# design.net
KiCad netlist of a schematic drawn in Altium Designer
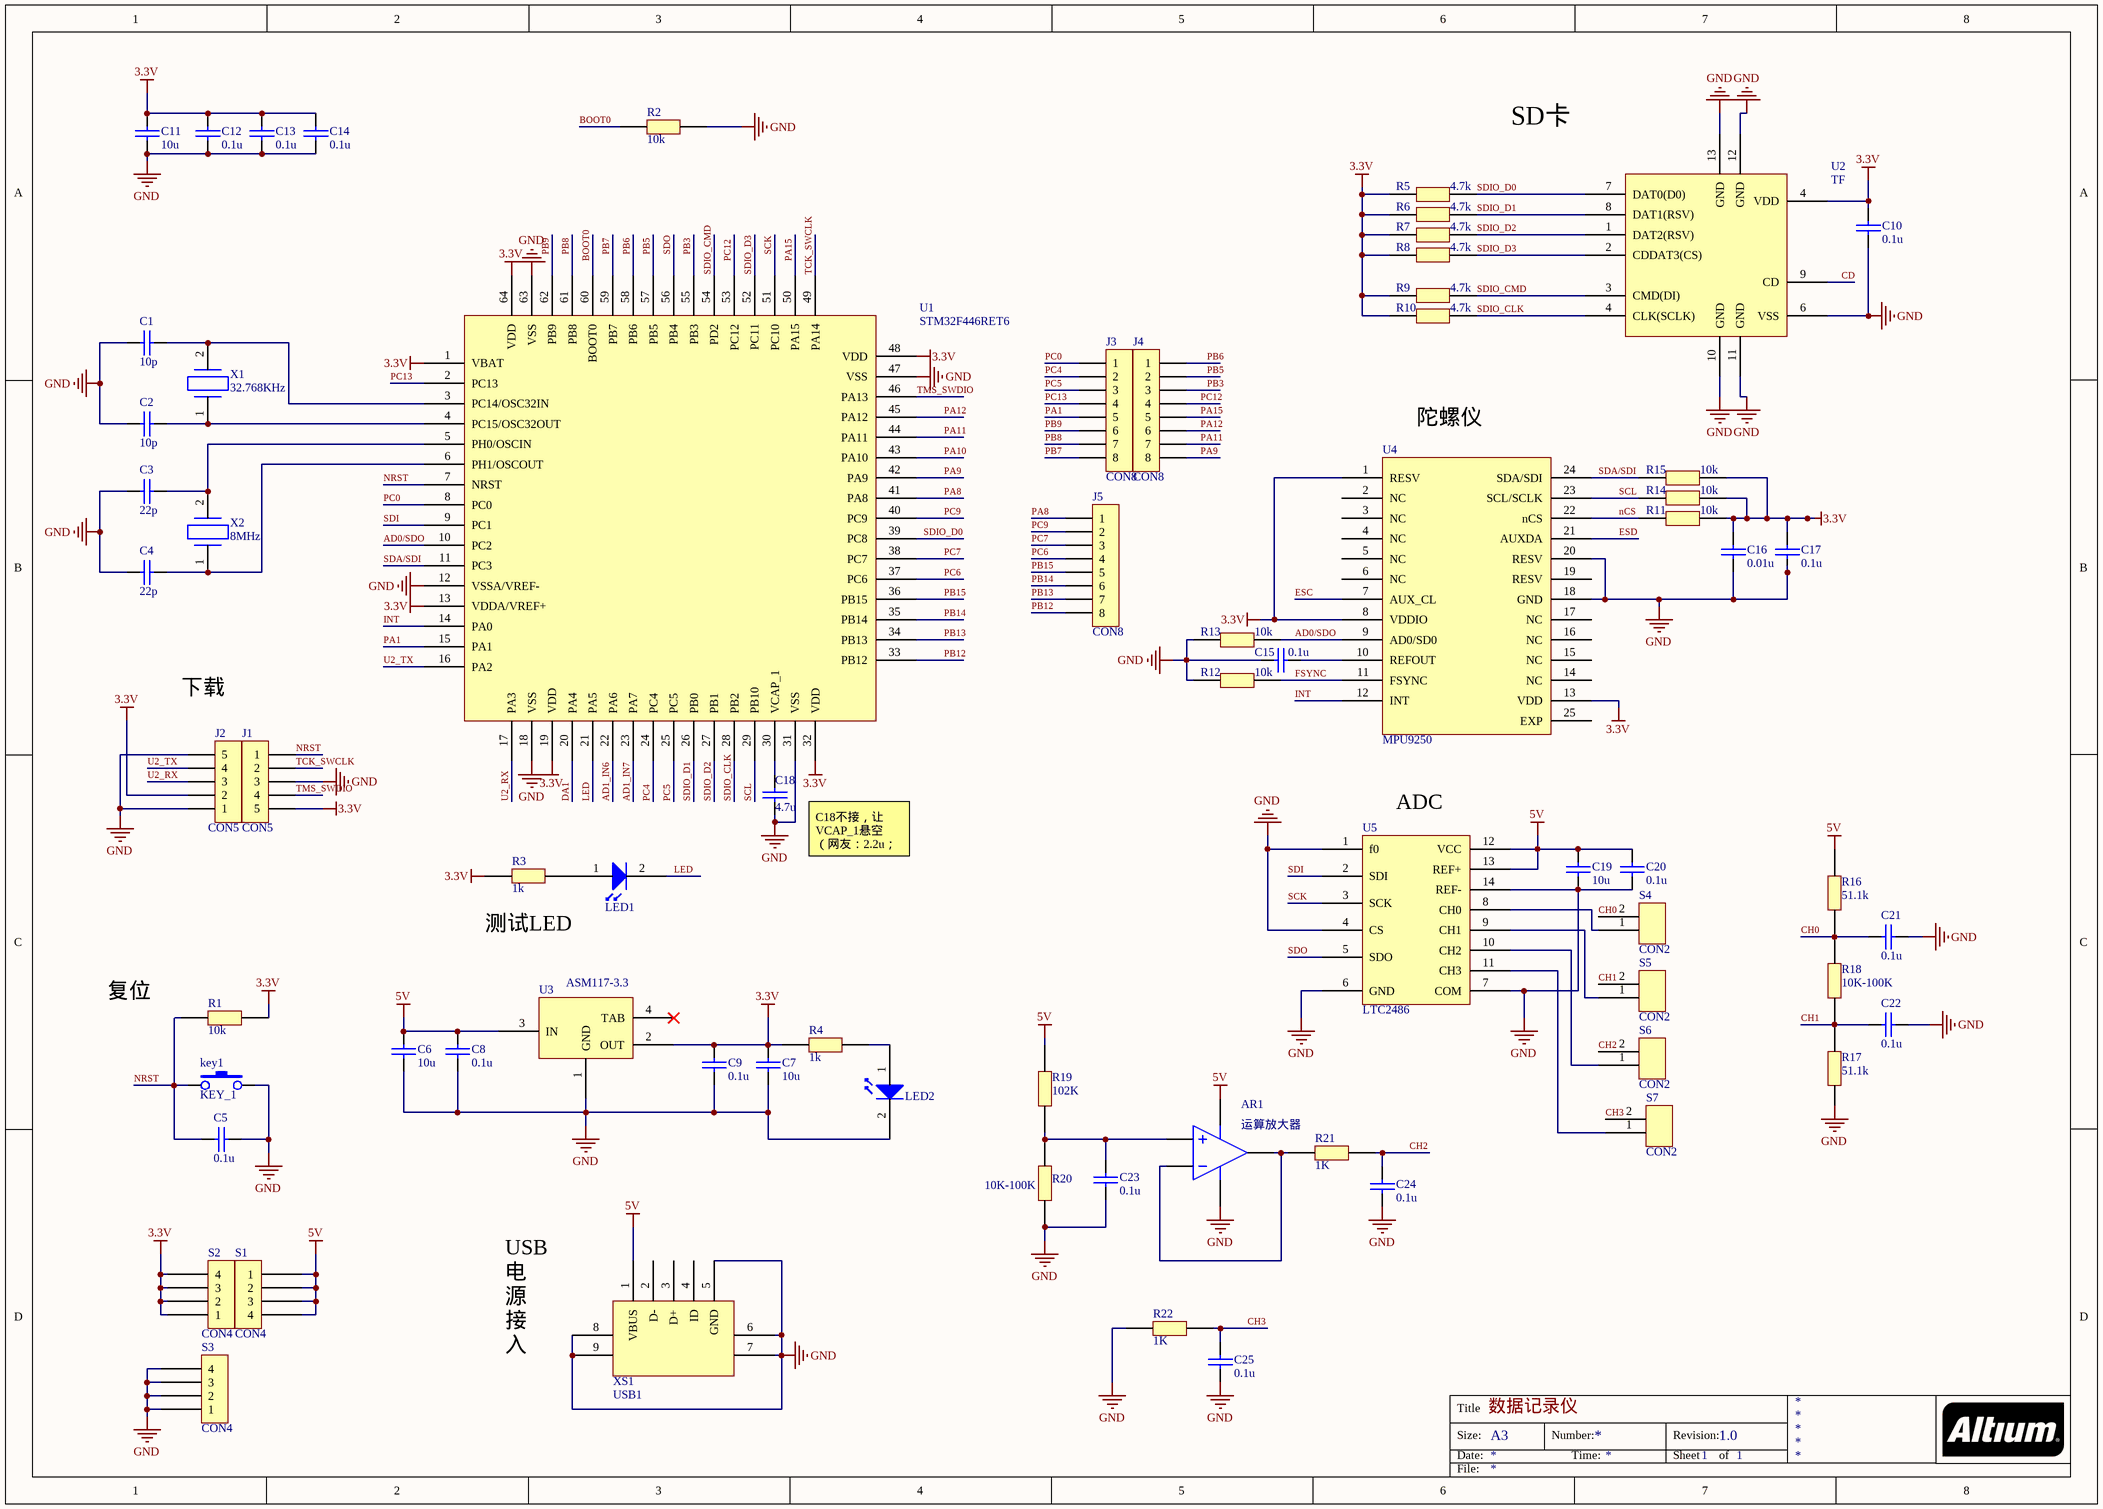
[diagram p0: 数据记录仪.SchDoc]

(export (version "E")
  (design (tool "Eeschema 10.0.6"))
  (components
    (comp (ref "AR1")
      (value "运算放大器")
      (footprint "MSOP-8")
      (description "Operational Amplifier")
      (libsource (lib "元件库") (part "运算放大器"))
    )
    (comp (ref "C1") (value "10p") (footprint "0603-cap") (libsource (lib "元件库") (part "CAP")))
    (comp (ref "C2") (value "10p") (footprint "0603-cap") (libsource (lib "元件库") (part "CAP")))
    (comp (ref "C3") (value "22p") (footprint "0603-cap") (libsource (lib "元件库") (part "CAP")))
    (comp (ref "C4") (value "22p") (footprint "0603-cap") (libsource (lib "元件库") (part "CAP")))
    (comp (ref "C5") (value "0.1u") (footprint "0603-cap") (libsource (lib "元件库") (part "CAP")))
    (comp (ref "C6") (value "10u") (footprint "0603-cap") (libsource (lib "元件库") (part "CAP")))
    (comp (ref "C7") (value "10u") (footprint "0603-cap") (libsource (lib "元件库") (part "CAP")))
    (comp (ref "C8") (value "0.1u") (footprint "0603-cap") (libsource (lib "元件库") (part "CAP")))
    (comp (ref "C9") (value "0.1u") (footprint "0603-cap") (libsource (lib "元件库") (part "CAP")))
    (comp (ref "C10") (value "0.1u") (footprint "0603-cap") (libsource (lib "元件库") (part "CAP")))
    (comp (ref "C11") (value "10u") (footprint "0603-cap") (libsource (lib "元件库") (part "CAP")))
    (comp (ref "C12") (value "0.1u") (footprint "0603-cap") (libsource (lib "元件库") (part "CAP")))
    (comp (ref "C13") (value "0.1u") (footprint "0603-cap") (libsource (lib "元件库") (part "CAP")))
    (comp (ref "C14") (value "0.1u") (footprint "0603-cap") (libsource (lib "元件库") (part "CAP")))
    (comp (ref "C15") (value "0.1u") (footprint "0603-cap") (libsource (lib "元件库") (part "CAP")))
    (comp (ref "C16") (value "0.01u") (footprint "0603-cap") (libsource (lib "元件库") (part "CAP")))
    (comp (ref "C17") (value "0.1u") (footprint "0603-cap") (libsource (lib "元件库") (part "CAP")))
    (comp (ref "C18") (value "4.7u") (footprint "0603-cap") (libsource (lib "元件库") (part "CAP")))
    (comp (ref "C19") (value "10u") (footprint "0603-cap") (libsource (lib "元件库") (part "CAP")))
    (comp (ref "C20") (value "0.1u") (footprint "0603-cap") (libsource (lib "元件库") (part "CAP")))
    (comp (ref "C21") (value "0.1u") (footprint "0603-cap") (libsource (lib "元件库") (part "CAP")))
    (comp (ref "C22") (value "0.1u") (footprint "0603-cap") (libsource (lib "元件库") (part "CAP")))
    (comp (ref "C23") (value "0.1u") (footprint "0603-cap") (libsource (lib "元件库") (part "CAP")))
    (comp (ref "C24") (value "0.1u") (footprint "0603-cap") (libsource (lib "元件库") (part "CAP")))
    (comp (ref "C25") (value "0.1u") (footprint "0603-cap") (libsource (lib "元件库") (part "CAP")))
    (comp (ref "J1") (value "CON5") (footprint "SIP05") (libsource (lib "") (part "CON5_1")))
    (comp (ref "J2") (value "CON5") (footprint "SIP05") (libsource (lib "元件库") (part "CON5")))
    (comp (ref "J3") (value "CON8") (footprint "SIP08") (libsource (lib "") (part "CON8_1")))
    (comp (ref "J4") (value "CON8") (footprint "SIP08") (libsource (lib "元件库") (part "CON8")))
    (comp (ref "J5") (value "CON8") (footprint "SIP08") (libsource (lib "") (part "CON8_1")))
    (comp (ref "key1") (value "KEY_1") (footprint "key - duplicate5") (libsource (lib "元件库") (part "KEY_1")))
    (comp (ref "LED1") (value "LED?") (footprint "LED") (libsource (lib "元件库") (part "LED")))
    (comp (ref "LED2") (value "LED?") (footprint "LED") (libsource (lib "元件库") (part "LED")))
    (comp (ref "R1") (value "10k") (footprint "0603-res") (libsource (lib "") (part "RES_1")))
    (comp (ref "R2") (value "10k") (footprint "0603-res") (libsource (lib "") (part "RES_1")))
    (comp (ref "R3") (value "1k") (footprint "0603-res") (libsource (lib "") (part "RES_1")))
    (comp (ref "R4") (value "1k") (footprint "0603-res") (libsource (lib "元件库") (part "RES")))
    (comp (ref "R5") (value "4.7k") (footprint "0603-res") (libsource (lib "元件库") (part "RES")))
    (comp (ref "R6") (value "4.7k") (footprint "0603-res") (libsource (lib "元件库") (part "RES")))
    (comp (ref "R7") (value "4.7k") (footprint "0603-res") (libsource (lib "元件库") (part "RES")))
    (comp (ref "R8") (value "4.7k") (footprint "0603-res") (libsource (lib "元件库") (part "RES")))
    (comp (ref "R9") (value "4.7k") (footprint "0603-res") (libsource (lib "元件库") (part "RES")))
    (comp (ref "R10") (value "4.7k") (footprint "0603-res") (libsource (lib "元件库") (part "RES")))
    (comp (ref "R11") (value "10k") (footprint "0603-res") (libsource (lib "元件库") (part "RES")))
    (comp (ref "R12") (value "10k") (footprint "0603-res") (libsource (lib "元件库") (part "RES")))
    (comp (ref "R13") (value "10k") (footprint "0603-res") (libsource (lib "元件库") (part "RES")))
    (comp (ref "R14") (value "10k") (footprint "0603-res") (libsource (lib "元件库") (part "RES")))
    (comp (ref "R15") (value "10k") (footprint "0603-res") (libsource (lib "元件库") (part "RES")))
    (comp (ref "R16") (value "51.1k") (footprint "0603-res") (libsource (lib "") (part "RES_2")))
    (comp (ref "R17") (value "51.1k") (footprint "0603-res") (libsource (lib "") (part "RES_2")))
    (comp (ref "R18") (value "10K-100K") (footprint "0603-res") (libsource (lib "") (part "RES_2")))
    (comp (ref "R19") (value "102K") (footprint "0603-res") (libsource (lib "") (part "RES_2")))
    (comp (ref "R20") (value "10K-100K") (footprint "0603-res") (libsource (lib "") (part "RES_2")))
    (comp (ref "R21") (value "1K") (footprint "0603-res") (libsource (lib "") (part "RES_1")))
    (comp (ref "R22") (value "1K") (footprint "0603-res") (libsource (lib "") (part "RES_1")))
    (comp (ref "S1") (value "CON4") (footprint "SIP04") (libsource (lib "") (part "CON4_1")))
    (comp (ref "S2") (value "CON4") (footprint "SIP04") (libsource (lib "元件库") (part "CON4")))
    (comp (ref "S3") (value "CON4") (footprint "SIP04") (libsource (lib "元件库") (part "CON4")))
    (comp (ref "S4") (value "CON2") (footprint "SIP02") (libsource (lib "元件库") (part "CON2")))
    (comp (ref "S5") (value "CON2") (footprint "SIP02") (libsource (lib "元件库") (part "CON2")))
    (comp (ref "S6") (value "CON2") (footprint "SIP02") (libsource (lib "元件库") (part "CON2")))
    (comp (ref "S7") (value "CON2") (footprint "SIP02") (libsource (lib "元件库") (part "CON2")))
    (comp (ref "U1")
      (value "STM32F446RET6")
      (footprint "LQFP-64_10X10X05P")
      (libsource (lib "元件库") (part "STM32F446RET6"))
    )
    (comp (ref "U2") (value "TF") (footprint "TF-01A") (libsource (lib "元件库") (part "TF-01A")))
    (comp (ref "U3") (value "ASM117-3.3") (footprint "SOT-223") (libsource (lib "元件库") (part "ASM117-3.3")))
    (comp (ref "U4")
      (value "MPU9250")
      (footprint "QFN-24-1EP_3X3MM_PITCH0.4MM")
      (libsource (lib "元件库") (part "MPU9250"))
    )
    (comp (ref "U5") (value "LTC2486") (footprint "DFN14") (libsource (lib "元件库") (part "LTC2486")))
    (comp (ref "X1") (value "32.768KHz") (footprint "XTAL2") (libsource (lib "元件库") (part "XTAL")))
    (comp (ref "X2") (value "8MHz") (footprint "XTAL2") (libsource (lib "元件库") (part "XTAL")))
    (comp (ref "XS1") (value "USB1") (footprint "micro USB") (libsource (lib "元件库") (part "USB1")))
  )
  (nets
    (net (code "1") (name "/AD0{slash}SDO") (class "Default")
      (node (ref "R13") (pin "2") (pinfunction "2_2") (pintype "passive"))
      (node (ref "U1") (pin "10") (pinfunction "PC2_10") (pintype "passive"))
      (node (ref "U4") (pin "9") (pinfunction "AD0/SD0_9") (pintype "passive"))
    )
    (net (code "2") (name "/AD1_IN6") (class "Default")
      (node (ref "U1") (pin "22") (pinfunction "PA6_22") (pintype "passive"))
    )
    (net (code "3") (name "/AD1_IN7") (class "Default")
      (node (ref "U1") (pin "23") (pinfunction "PA7_23") (pintype "passive"))
    )
    (net (code "4") (name "/BOOT0") (class "Default")
      (node (ref "R2") (pin "2") (pinfunction "2_2") (pintype "passive"))
      (node (ref "U1") (pin "60") (pinfunction "BOOT0_60") (pintype "passive"))
    )
    (net (code "5") (name "/CD") (class "Default")
      (node (ref "U2") (pin "9") (pinfunction "CD_9") (pintype "passive"))
    )
    (net (code "6") (name "/CH0") (class "Default")
      (node (ref "C21") (pin "1") (pinfunction "1_1") (pintype "passive"))
      (node (ref "R16") (pin "1") (pinfunction "1_1") (pintype "passive"))
      (node (ref "R18") (pin "2") (pinfunction "2_2") (pintype "passive"))
      (node (ref "S4") (pin "2") (pinfunction "2_2") (pintype "passive"))
    )
    (net (code "7") (name "/CH1") (class "Default")
      (node (ref "C22") (pin "2") (pinfunction "2_2") (pintype "passive"))
      (node (ref "R17") (pin "2") (pinfunction "2_2") (pintype "passive"))
      (node (ref "R18") (pin "1") (pinfunction "1_1") (pintype "passive"))
      (node (ref "S5") (pin "2") (pinfunction "2_2") (pintype "passive"))
    )
    (net (code "8") (name "/CH2") (class "Default")
      (node (ref "C24") (pin "1") (pinfunction "1_1") (pintype "passive"))
      (node (ref "R21") (pin "1") (pinfunction "1_1") (pintype "passive"))
      (node (ref "S6") (pin "2") (pinfunction "2_2") (pintype "passive"))
    )
    (net (code "9") (name "/CH3") (class "Default")
      (node (ref "C25") (pin "1") (pinfunction "1_1") (pintype "passive"))
      (node (ref "R22") (pin "1") (pinfunction "1_1") (pintype "passive"))
      (node (ref "S7") (pin "2") (pinfunction "2_2") (pintype "passive"))
    )
    (net (code "10") (name "/DA1") (class "Default")
      (node (ref "U1") (pin "20") (pinfunction "PA4_20") (pintype "passive"))
    )
    (net (code "11") (name "/ESC") (class "Default")
      (node (ref "U4") (pin "7") (pinfunction "AUX_CL_7") (pintype "passive"))
    )
    (net (code "12") (name "/ESD") (class "Default")
      (node (ref "U4") (pin "21") (pinfunction "AUXDA_21") (pintype "passive"))
    )
    (net (code "13") (name "/FSYNC") (class "Default")
      (node (ref "R12") (pin "2") (pinfunction "2_2") (pintype "passive"))
      (node (ref "U4") (pin "11") (pinfunction "FSYNC_11") (pintype "passive"))
    )
    (net (code "14") (name "/INT") (class "Default")
      (node (ref "U1") (pin "14") (pinfunction "PA0_14") (pintype "passive"))
      (node (ref "U4") (pin "12") (pinfunction "INT_12") (pintype "passive"))
    )
    (net (code "15") (name "/LED") (class "Default")
      (node (ref "LED1") (pin "2") (pinfunction "2_2") (pintype "passive"))
      (node (ref "U1") (pin "21") (pinfunction "PA5_21") (pintype "passive"))
    )
    (net (code "16") (name "/NRST") (class "Default")
      (node (ref "C5") (pin "1") (pinfunction "1_1") (pintype "passive"))
      (node (ref "J1") (pin "1") (pinfunction "1_1") (pintype "passive"))
      (node (ref "R1") (pin "2") (pinfunction "2_2") (pintype "passive"))
      (node (ref "U1") (pin "7") (pinfunction "NRST_7") (pintype "passive"))
      (node (ref "key1") (pin "1") (pinfunction "1_1") (pintype "passive"))
    )
    (net (code "17") (name "/PA1") (class "Default")
      (node (ref "J3") (pin "5") (pinfunction "5_5") (pintype "passive"))
      (node (ref "U1") (pin "15") (pinfunction "PA1_15") (pintype "passive"))
    )
    (net (code "18") (name "/PA8") (class "Default")
      (node (ref "J5") (pin "1") (pinfunction "1_1") (pintype "passive"))
      (node (ref "U1") (pin "41") (pinfunction "PA8_41") (pintype "passive"))
    )
    (net (code "19") (name "/PA9") (class "Default")
      (node (ref "J4") (pin "8") (pinfunction "8_8") (pintype "passive"))
      (node (ref "U1") (pin "42") (pinfunction "PA9_42") (pintype "passive"))
    )
    (net (code "20") (name "/PA10") (class "Default")
      (node (ref "U1") (pin "43") (pinfunction "PA10_43") (pintype "passive"))
    )
    (net (code "21") (name "/PA11") (class "Default")
      (node (ref "J4") (pin "7") (pinfunction "7_7") (pintype "passive"))
      (node (ref "U1") (pin "44") (pinfunction "PA11_44") (pintype "passive"))
    )
    (net (code "22") (name "/PA12") (class "Default")
      (node (ref "J4") (pin "6") (pinfunction "6_6") (pintype "passive"))
      (node (ref "U1") (pin "45") (pinfunction "PA12_45") (pintype "passive"))
    )
    (net (code "23") (name "/PA15") (class "Default")
      (node (ref "J4") (pin "5") (pinfunction "5_5") (pintype "passive"))
      (node (ref "U1") (pin "50") (pinfunction "PA15_50") (pintype "passive"))
    )
    (net (code "24") (name "/PB3") (class "Default")
      (node (ref "J4") (pin "3") (pinfunction "3_3") (pintype "passive"))
      (node (ref "U1") (pin "55") (pinfunction "PB3_55") (pintype "passive"))
    )
    (net (code "25") (name "/PB5") (class "Default")
      (node (ref "J4") (pin "2") (pinfunction "2_2") (pintype "passive"))
      (node (ref "U1") (pin "57") (pinfunction "PB5_57") (pintype "passive"))
    )
    (net (code "26") (name "/PB6") (class "Default")
      (node (ref "J4") (pin "1") (pinfunction "1_1") (pintype "passive"))
      (node (ref "U1") (pin "58") (pinfunction "PB6_58") (pintype "passive"))
    )
    (net (code "27") (name "/PB7") (class "Default")
      (node (ref "J3") (pin "8") (pinfunction "8_8") (pintype "passive"))
      (node (ref "U1") (pin "59") (pinfunction "PB7_59") (pintype "passive"))
    )
    (net (code "28") (name "/PB8") (class "Default")
      (node (ref "J3") (pin "7") (pinfunction "7_7") (pintype "passive"))
      (node (ref "U1") (pin "61") (pinfunction "PB8_61") (pintype "passive"))
    )
    (net (code "29") (name "/PB9") (class "Default")
      (node (ref "J3") (pin "6") (pinfunction "6_6") (pintype "passive"))
      (node (ref "U1") (pin "62") (pinfunction "PB9_62") (pintype "passive"))
    )
    (net (code "30") (name "/PB12") (class "Default")
      (node (ref "J5") (pin "8") (pinfunction "8_8") (pintype "passive"))
      (node (ref "U1") (pin "33") (pinfunction "PB12_33") (pintype "passive"))
    )
    (net (code "31") (name "/PB13") (class "Default")
      (node (ref "J5") (pin "7") (pinfunction "7_7") (pintype "passive"))
      (node (ref "U1") (pin "34") (pinfunction "PB13_34") (pintype "passive"))
    )
    (net (code "32") (name "/PB14") (class "Default")
      (node (ref "J5") (pin "6") (pinfunction "6_6") (pintype "passive"))
      (node (ref "U1") (pin "35") (pinfunction "PB14_35") (pintype "passive"))
    )
    (net (code "33") (name "/PB15") (class "Default")
      (node (ref "J5") (pin "5") (pinfunction "5_5") (pintype "passive"))
      (node (ref "U1") (pin "36") (pinfunction "PB15_36") (pintype "passive"))
    )
    (net (code "34") (name "/PC0") (class "Default")
      (node (ref "J3") (pin "1") (pinfunction "1_1") (pintype "passive"))
      (node (ref "U1") (pin "8") (pinfunction "PC0_8") (pintype "passive"))
    )
    (net (code "35") (name "/PC4") (class "Default")
      (node (ref "J3") (pin "2") (pinfunction "2_2") (pintype "passive"))
      (node (ref "U1") (pin "24") (pinfunction "PC4_24") (pintype "passive"))
    )
    (net (code "36") (name "/PC5") (class "Default")
      (node (ref "J3") (pin "3") (pinfunction "3_3") (pintype "passive"))
      (node (ref "U1") (pin "25") (pinfunction "PC5_25") (pintype "passive"))
    )
    (net (code "37") (name "/PC6") (class "Default")
      (node (ref "J5") (pin "4") (pinfunction "4_4") (pintype "passive"))
      (node (ref "U1") (pin "37") (pinfunction "PC6_37") (pintype "passive"))
    )
    (net (code "38") (name "/PC7") (class "Default")
      (node (ref "J5") (pin "3") (pinfunction "3_3") (pintype "passive"))
      (node (ref "U1") (pin "38") (pinfunction "PC7_38") (pintype "passive"))
    )
    (net (code "39") (name "/PC9") (class "Default")
      (node (ref "J5") (pin "2") (pinfunction "2_2") (pintype "passive"))
      (node (ref "U1") (pin "40") (pinfunction "PC9_40") (pintype "passive"))
    )
    (net (code "40") (name "/PC12") (class "Default")
      (node (ref "J4") (pin "4") (pinfunction "4_4") (pintype "passive"))
      (node (ref "U1") (pin "53") (pinfunction "PC12_53") (pintype "passive"))
    )
    (net (code "41") (name "/PC13") (class "Default")
      (node (ref "J3") (pin "4") (pinfunction "4_4") (pintype "passive"))
      (node (ref "U1") (pin "2") (pinfunction "PC13_2") (pintype "passive"))
    )
    (net (code "42") (name "/SCK") (class "Default")
      (node (ref "U1") (pin "51") (pinfunction "PC10_51") (pintype "passive"))
      (node (ref "U5") (pin "3") (pinfunction "SCK_3") (pintype "passive"))
    )
    (net (code "43") (name "/SCL") (class "Default")
      (node (ref "R14") (pin "1") (pinfunction "1_1") (pintype "passive"))
      (node (ref "U1") (pin "29") (pinfunction "PB10_29") (pintype "passive"))
      (node (ref "U4") (pin "23") (pinfunction "SCL/SCLK_23") (pintype "passive"))
    )
    (net (code "44") (name "/SDA{slash}SDI") (class "Default")
      (node (ref "R15") (pin "1") (pinfunction "1_1") (pintype "passive"))
      (node (ref "U1") (pin "11") (pinfunction "PC3_11") (pintype "passive"))
      (node (ref "U4") (pin "24") (pinfunction "SDA/SDI_24") (pintype "passive"))
    )
    (net (code "45") (name "/SDI") (class "Default")
      (node (ref "U1") (pin "9") (pinfunction "PC1_9") (pintype "passive"))
      (node (ref "U5") (pin "2") (pinfunction "SDI_2") (pintype "passive"))
    )
    (net (code "46") (name "/SDIO_CLK") (class "Default")
      (node (ref "R10") (pin "2") (pinfunction "2_2") (pintype "passive"))
      (node (ref "U1") (pin "28") (pinfunction "PB2_28") (pintype "passive"))
      (node (ref "U2") (pin "4") (pinfunction "CLK(SCLK)_4") (pintype "passive"))
    )
    (net (code "47") (name "/SDIO_CMD") (class "Default")
      (node (ref "R9") (pin "2") (pinfunction "2_2") (pintype "passive"))
      (node (ref "U1") (pin "54") (pinfunction "PD2_54") (pintype "passive"))
      (node (ref "U2") (pin "3") (pinfunction "CMD(DI)_3") (pintype "passive"))
    )
    (net (code "48") (name "/SDIO_D0") (class "Default")
      (node (ref "R5") (pin "2") (pinfunction "2_2") (pintype "passive"))
      (node (ref "U1") (pin "39") (pinfunction "PC8_39") (pintype "passive"))
      (node (ref "U2") (pin "7") (pinfunction "DAT0(D0)_7") (pintype "passive"))
    )
    (net (code "49") (name "/SDIO_D1") (class "Default")
      (node (ref "R6") (pin "2") (pinfunction "2_2") (pintype "passive"))
      (node (ref "U1") (pin "26") (pinfunction "PB0_26") (pintype "passive"))
      (node (ref "U2") (pin "8") (pinfunction "DAT1(RSV)_8") (pintype "passive"))
    )
    (net (code "50") (name "/SDIO_D2") (class "Default")
      (node (ref "R7") (pin "2") (pinfunction "2_2") (pintype "passive"))
      (node (ref "U1") (pin "27") (pinfunction "PB1_27") (pintype "passive"))
      (node (ref "U2") (pin "1") (pinfunction "DAT2(RSV)_1") (pintype "passive"))
    )
    (net (code "51") (name "/SDIO_D3") (class "Default")
      (node (ref "R8") (pin "2") (pinfunction "2_2") (pintype "passive"))
      (node (ref "U1") (pin "52") (pinfunction "PC11_52") (pintype "passive"))
      (node (ref "U2") (pin "2") (pinfunction "CDDAT3(CS)_2") (pintype "passive"))
    )
    (net (code "52") (name "/SDO") (class "Default")
      (node (ref "U1") (pin "56") (pinfunction "PB4_56") (pintype "passive"))
      (node (ref "U5") (pin "5") (pinfunction "SDO_5") (pintype "passive"))
    )
    (net (code "53") (name "/TCK_SWCLK") (class "Default")
      (node (ref "J1") (pin "2") (pinfunction "2_2") (pintype "passive"))
      (node (ref "U1") (pin "49") (pinfunction "PA14_49") (pintype "passive"))
    )
    (net (code "54") (name "/TMS_SWDIO") (class "Default")
      (node (ref "J1") (pin "4") (pinfunction "4_4") (pintype "passive"))
      (node (ref "U1") (pin "46") (pinfunction "PA13_46") (pintype "passive"))
    )
    (net (code "55") (name "/U2_RX") (class "Default")
      (node (ref "J2") (pin "3") (pinfunction "3_3") (pintype "passive"))
      (node (ref "U1") (pin "17") (pinfunction "PA3_17") (pintype "passive"))
    )
    (net (code "56") (name "/U2_TX") (class "Default")
      (node (ref "J2") (pin "4") (pinfunction "4_4") (pintype "passive"))
      (node (ref "U1") (pin "16") (pinfunction "PA2_16") (pintype "passive"))
    )
    (net (code "57") (name "/nCS") (class "Default")
      (node (ref "R11") (pin "1") (pinfunction "1_1") (pintype "passive"))
      (node (ref "U4") (pin "22") (pinfunction "nCS_22") (pintype "passive"))
    )
    (net (code "58") (name "3.3V") (class "Default")
      (node (ref "C10") (pin "1") (pinfunction "1_1") (pintype "passive"))
      (node (ref "C11") (pin "1") (pinfunction "1_1") (pintype "passive"))
      (node (ref "C12") (pin "1") (pinfunction "1_1") (pintype "passive"))
      (node (ref "C13") (pin "1") (pinfunction "1_1") (pintype "passive"))
      (node (ref "C14") (pin "1") (pinfunction "1_1") (pintype "passive"))
      (node (ref "C16") (pin "2") (pinfunction "2_2") (pintype "passive"))
      (node (ref "C17") (pin "2") (pinfunction "2_2") (pintype "passive"))
      (node (ref "C7") (pin "1") (pinfunction "1_1") (pintype "passive"))
      (node (ref "C9") (pin "1") (pinfunction "1_1") (pintype "passive"))
      (node (ref "J1") (pin "5") (pinfunction "5_5") (pintype "passive"))
      (node (ref "J2") (pin "2") (pinfunction "2_2") (pintype "passive"))
      (node (ref "R1") (pin "1") (pinfunction "1_1") (pintype "passive"))
      (node (ref "R10") (pin "1") (pinfunction "1_1") (pintype "passive"))
      (node (ref "R11") (pin "2") (pinfunction "2_2") (pintype "passive"))
      (node (ref "R14") (pin "2") (pinfunction "2_2") (pintype "passive"))
      (node (ref "R15") (pin "2") (pinfunction "2_2") (pintype "passive"))
      (node (ref "R3") (pin "2") (pinfunction "2_2") (pintype "passive"))
      (node (ref "R4") (pin "1") (pinfunction "1_1") (pintype "passive"))
      (node (ref "R5") (pin "1") (pinfunction "1_1") (pintype "passive"))
      (node (ref "R6") (pin "1") (pinfunction "1_1") (pintype "passive"))
      (node (ref "R7") (pin "1") (pinfunction "1_1") (pintype "passive"))
      (node (ref "R8") (pin "1") (pinfunction "1_1") (pintype "passive"))
      (node (ref "R9") (pin "1") (pinfunction "1_1") (pintype "passive"))
      (node (ref "S2") (pin "1") (pinfunction "1_1") (pintype "passive"))
      (node (ref "S2") (pin "2") (pinfunction "2_2") (pintype "passive"))
      (node (ref "S2") (pin "3") (pinfunction "3_3") (pintype "passive"))
      (node (ref "S2") (pin "4") (pinfunction "4_4") (pintype "passive"))
      (node (ref "U1") (pin "1") (pinfunction "VBAT_1") (pintype "passive"))
      (node (ref "U1") (pin "13") (pinfunction "VDDA/VREF+_13") (pintype "passive"))
      (node (ref "U1") (pin "19") (pinfunction "VDD_19") (pintype "passive"))
      (node (ref "U1") (pin "32") (pinfunction "VDD_32") (pintype "passive"))
      (node (ref "U1") (pin "48") (pinfunction "VDD_48") (pintype "passive"))
      (node (ref "U1") (pin "64") (pinfunction "VDD_64") (pintype "passive"))
      (node (ref "U2") (pin "4") (pinfunction "VDD_4") (pintype "passive"))
      (node (ref "U3") (pin "2") (pinfunction "OUT_2") (pintype "passive"))
      (node (ref "U4") (pin "1") (pinfunction "RESV_1") (pintype "passive"))
      (node (ref "U4") (pin "13") (pinfunction "VDD_13") (pintype "passive"))
      (node (ref "U4") (pin "8") (pinfunction "VDDIO_8") (pintype "passive"))
    )
    (net (code "59") (name "5V") (class "Default")
      (node (ref "AR1") (pin "5") (pinfunction "V-_5") (pintype "passive"))
      (node (ref "C19") (pin "2") (pinfunction "2_2") (pintype "passive"))
      (node (ref "C20") (pin "2") (pinfunction "2_2") (pintype "passive"))
      (node (ref "C6") (pin "1") (pinfunction "1_1") (pintype "passive"))
      (node (ref "C8") (pin "1") (pinfunction "1_1") (pintype "passive"))
      (node (ref "R16") (pin "2") (pinfunction "2_2") (pintype "passive"))
      (node (ref "R19") (pin "2") (pinfunction "2_2") (pintype "passive"))
      (node (ref "S1") (pin "1") (pinfunction "1_1") (pintype "passive"))
      (node (ref "S1") (pin "2") (pinfunction "2_2") (pintype "passive"))
      (node (ref "S1") (pin "3") (pinfunction "3_3") (pintype "passive"))
      (node (ref "S1") (pin "4") (pinfunction "4_4") (pintype "passive"))
      (node (ref "U3") (pin "3") (pinfunction "IN_3") (pintype "passive"))
      (node (ref "U5") (pin "12") (pinfunction "VCC_12") (pintype "passive"))
      (node (ref "U5") (pin "13") (pinfunction "REF+_13") (pintype "passive"))
      (node (ref "XS1") (pin "1") (pinfunction "VBUS_1") (pintype "passive"))
    )
    (net (code "60") (name "GND") (class "Default")
      (node (ref "AR1") (pin "4") (pinfunction "V+_4") (pintype "passive"))
      (node (ref "C1") (pin "1") (pinfunction "1_1") (pintype "passive"))
      (node (ref "C10") (pin "2") (pinfunction "2_2") (pintype "passive"))
      (node (ref "C11") (pin "2") (pinfunction "2_2") (pintype "passive"))
      (node (ref "C12") (pin "2") (pinfunction "2_2") (pintype "passive"))
      (node (ref "C13") (pin "2") (pinfunction "2_2") (pintype "passive"))
      (node (ref "C14") (pin "2") (pinfunction "2_2") (pintype "passive"))
      (node (ref "C15") (pin "1") (pinfunction "1_1") (pintype "passive"))
      (node (ref "C16") (pin "1") (pinfunction "1_1") (pintype "passive"))
      (node (ref "C17") (pin "1") (pinfunction "1_1") (pintype "passive"))
      (node (ref "C18") (pin "1") (pinfunction "1_1") (pintype "passive"))
      (node (ref "C19") (pin "1") (pinfunction "1_1") (pintype "passive"))
      (node (ref "C2") (pin "1") (pinfunction "1_1") (pintype "passive"))
      (node (ref "C20") (pin "1") (pinfunction "1_1") (pintype "passive"))
      (node (ref "C21") (pin "2") (pinfunction "2_2") (pintype "passive"))
      (node (ref "C22") (pin "1") (pinfunction "1_1") (pintype "passive"))
      (node (ref "C23") (pin "2") (pinfunction "2_2") (pintype "passive"))
      (node (ref "C24") (pin "2") (pinfunction "2_2") (pintype "passive"))
      (node (ref "C25") (pin "2") (pinfunction "2_2") (pintype "passive"))
      (node (ref "C3") (pin "1") (pinfunction "1_1") (pintype "passive"))
      (node (ref "C4") (pin "1") (pinfunction "1_1") (pintype "passive"))
      (node (ref "C5") (pin "2") (pinfunction "2_2") (pintype "passive"))
      (node (ref "C6") (pin "2") (pinfunction "2_2") (pintype "passive"))
      (node (ref "C7") (pin "2") (pinfunction "2_2") (pintype "passive"))
      (node (ref "C8") (pin "2") (pinfunction "2_2") (pintype "passive"))
      (node (ref "C9") (pin "2") (pinfunction "2_2") (pintype "passive"))
      (node (ref "J1") (pin "3") (pinfunction "3_3") (pintype "passive"))
      (node (ref "J2") (pin "1") (pinfunction "1_1") (pintype "passive"))
      (node (ref "J2") (pin "5") (pinfunction "5_5") (pintype "passive"))
      (node (ref "LED2") (pin "2") (pinfunction "2_2") (pintype "passive"))
      (node (ref "R12") (pin "1") (pinfunction "1_1") (pintype "passive"))
      (node (ref "R13") (pin "1") (pinfunction "1_1") (pintype "passive"))
      (node (ref "R2") (pin "1") (pinfunction "1_1") (pintype "passive"))
      (node (ref "R20") (pin "1") (pinfunction "1_1") (pintype "passive"))
      (node (ref "R22") (pin "2") (pinfunction "2_2") (pintype "passive"))
      (node (ref "S3") (pin "1") (pinfunction "1_1") (pintype "passive"))
      (node (ref "S3") (pin "2") (pinfunction "2_2") (pintype "passive"))
      (node (ref "S3") (pin "3") (pinfunction "3_3") (pintype "passive"))
      (node (ref "S3") (pin "4") (pinfunction "4_4") (pintype "passive"))
      (node (ref "U1") (pin "12") (pinfunction "VSSA/VREF-_12") (pintype "passive"))
      (node (ref "U1") (pin "18") (pinfunction "VSS_18") (pintype "passive"))
      (node (ref "U1") (pin "31") (pinfunction "VSS_31") (pintype "passive"))
      (node (ref "U1") (pin "47") (pinfunction "VSS_47") (pintype "passive"))
      (node (ref "U1") (pin "63") (pinfunction "VSS_63") (pintype "passive"))
      (node (ref "U2") (pin "10") (pinfunction "GND_10") (pintype "passive"))
      (node (ref "U2") (pin "11") (pinfunction "GND_11") (pintype "passive"))
      (node (ref "U2") (pin "12") (pinfunction "GND_12") (pintype "passive"))
      (node (ref "U2") (pin "13") (pinfunction "GND_13") (pintype "passive"))
      (node (ref "U2") (pin "6") (pinfunction "VSS_6") (pintype "passive"))
      (node (ref "U3") (pin "1") (pinfunction "GND_1") (pintype "passive"))
      (node (ref "U4") (pin "18") (pinfunction "GND_18") (pintype "passive"))
      (node (ref "U4") (pin "20") (pinfunction "RESV_20") (pintype "passive"))
      (node (ref "U5") (pin "1") (pinfunction "f0_1") (pintype "passive"))
      (node (ref "U5") (pin "14") (pinfunction "REF-_14") (pintype "passive"))
      (node (ref "U5") (pin "4") (pinfunction "CS_4") (pintype "passive"))
      (node (ref "U5") (pin "6") (pinfunction "GND_6") (pintype "passive"))
      (node (ref "U5") (pin "7") (pinfunction "COM_7") (pintype "passive"))
      (node (ref "XS1") (pin "5") (pinfunction "GND_5") (pintype "passive"))
      (node (ref "XS1") (pin "6") (pinfunction "6_6") (pintype "passive"))
      (node (ref "XS1") (pin "7") (pinfunction "7_7") (pintype "passive"))
      (node (ref "XS1") (pin "8") (pinfunction "8_8") (pintype "passive"))
      (node (ref "XS1") (pin "9") (pinfunction "9_9") (pintype "passive"))
      (node (ref "key1") (pin "2") (pinfunction "2_2") (pintype "passive"))
    )
    (net (code "61") (name "Net-(AR1-IN+)") (class "Default")
      (node (ref "AR1") (pin "2") (pinfunction "IN+_2") (pintype "passive"))
      (node (ref "C23") (pin "1") (pinfunction "1_1") (pintype "passive"))
      (node (ref "R19") (pin "1") (pinfunction "1_1") (pintype "passive"))
      (node (ref "R20") (pin "2") (pinfunction "2_2") (pintype "passive"))
    )
    (net (code "62") (name "Net-(AR1-IN-)") (class "Default")
      (node (ref "AR1") (pin "1") (pinfunction "IN-_1") (pintype "passive"))
      (node (ref "AR1") (pin "3") (pinfunction "OUT_3") (pintype "passive"))
      (node (ref "R21") (pin "2") (pinfunction "2_2") (pintype "passive"))
    )
    (net (code "63") (name "Net-(LED1-Pad1)") (class "Default")
      (node (ref "LED1") (pin "1") (pinfunction "1_1") (pintype "passive"))
      (node (ref "R3") (pin "1") (pinfunction "1_1") (pintype "passive"))
    )
    (net (code "64") (name "Net-(LED2-Pad1)") (class "Default")
      (node (ref "LED2") (pin "1") (pinfunction "1_1") (pintype "passive"))
      (node (ref "R4") (pin "2") (pinfunction "2_2") (pintype "passive"))
    )
    (net (code "65") (name "Net-(U1-PC14{slash}OSC32IN)") (class "Default")
      (node (ref "C1") (pin "2") (pinfunction "2_2") (pintype "passive"))
      (node (ref "U1") (pin "3") (pinfunction "PC14/OSC32IN_3") (pintype "passive"))
      (node (ref "X1") (pin "2") (pinfunction "2_2") (pintype "passive"))
    )
    (net (code "66") (name "Net-(U1-PC15{slash}OSC32OUT)") (class "Default")
      (node (ref "C2") (pin "2") (pinfunction "2_2") (pintype "passive"))
      (node (ref "U1") (pin "4") (pinfunction "PC15/OSC32OUT_4") (pintype "passive"))
      (node (ref "X1") (pin "1") (pinfunction "1_1") (pintype "passive"))
    )
    (net (code "67") (name "Net-(U1-PH0{slash}OSCIN)") (class "Default")
      (node (ref "C3") (pin "2") (pinfunction "2_2") (pintype "passive"))
      (node (ref "U1") (pin "5") (pinfunction "PH0/OSCIN_5") (pintype "passive"))
      (node (ref "X2") (pin "2") (pinfunction "2_2") (pintype "passive"))
    )
    (net (code "68") (name "Net-(U1-PH1{slash}OSCOUT)") (class "Default")
      (node (ref "C4") (pin "2") (pinfunction "2_2") (pintype "passive"))
      (node (ref "U1") (pin "6") (pinfunction "PH1/OSCOUT_6") (pintype "passive"))
      (node (ref "X2") (pin "1") (pinfunction "1_1") (pintype "passive"))
    )
    (net (code "69") (name "Net-(U1-VCAP_1)") (class "Default")
      (node (ref "C18") (pin "2") (pinfunction "2_2") (pintype "passive"))
      (node (ref "U1") (pin "30") (pinfunction "VCAP_1_30") (pintype "passive"))
    )
    (net (code "70") (name "Net-(U4-REFOUT)") (class "Default")
      (node (ref "C15") (pin "2") (pinfunction "2_2") (pintype "passive"))
      (node (ref "U4") (pin "10") (pinfunction "REFOUT_10") (pintype "passive"))
    )
    (net (code "71") (name "Net-(U5-CH0)") (class "Default")
      (node (ref "S4") (pin "1") (pinfunction "1_1") (pintype "passive"))
      (node (ref "U5") (pin "8") (pinfunction "CH0_8") (pintype "passive"))
    )
    (net (code "72") (name "Net-(U5-CH1)") (class "Default")
      (node (ref "S5") (pin "1") (pinfunction "1_1") (pintype "passive"))
      (node (ref "U5") (pin "9") (pinfunction "CH1_9") (pintype "passive"))
    )
    (net (code "73") (name "Net-(U5-CH2)") (class "Default")
      (node (ref "S6") (pin "1") (pinfunction "1_1") (pintype "passive"))
      (node (ref "U5") (pin "10") (pinfunction "CH2_10") (pintype "passive"))
    )
    (net (code "74") (name "Net-(U5-CH3)") (class "Default")
      (node (ref "S7") (pin "1") (pinfunction "1_1") (pintype "passive"))
      (node (ref "U5") (pin "11") (pinfunction "CH3_11") (pintype "passive"))
    )
    (net (code "75") (name "unconnected-(R17-Pad1)") (class "Default")
      (node (ref "R17") (pin "1") (pinfunction "1_1") (pintype "passive"))
    )
    (net (code "76") (name "unconnected-(U3-TAB-Pad4)") (class "Default")
      (node (ref "U3") (pin "4") (pinfunction "TAB_4") (pintype "passive+no_connect"))
    )
    (net (code "77") (name "unconnected-(U4-EXP-Pad25)") (class "Default")
      (node (ref "U4") (pin "25") (pinfunction "EXP_25") (pintype "passive"))
    )
    (net (code "78") (name "unconnected-(U4-NC-Pad2)") (class "Default")
      (node (ref "U4") (pin "2") (pinfunction "NC_2") (pintype "passive"))
    )
    (net (code "79") (name "unconnected-(U4-NC-Pad3)") (class "Default")
      (node (ref "U4") (pin "3") (pinfunction "NC_3") (pintype "passive"))
    )
    (net (code "80") (name "unconnected-(U4-NC-Pad4)") (class "Default")
      (node (ref "U4") (pin "4") (pinfunction "NC_4") (pintype "passive"))
    )
    (net (code "81") (name "unconnected-(U4-NC-Pad5)") (class "Default")
      (node (ref "U4") (pin "5") (pinfunction "NC_5") (pintype "passive"))
    )
    (net (code "82") (name "unconnected-(U4-NC-Pad6)") (class "Default")
      (node (ref "U4") (pin "6") (pinfunction "NC_6") (pintype "passive"))
    )
    (net (code "83") (name "unconnected-(U4-NC-Pad14)") (class "Default")
      (node (ref "U4") (pin "14") (pinfunction "NC_14") (pintype "passive"))
    )
    (net (code "84") (name "unconnected-(U4-NC-Pad15)") (class "Default")
      (node (ref "U4") (pin "15") (pinfunction "NC_15") (pintype "passive"))
    )
    (net (code "85") (name "unconnected-(U4-NC-Pad16)") (class "Default")
      (node (ref "U4") (pin "16") (pinfunction "NC_16") (pintype "passive"))
    )
    (net (code "86") (name "unconnected-(U4-NC-Pad17)") (class "Default")
      (node (ref "U4") (pin "17") (pinfunction "NC_17") (pintype "passive"))
    )
    (net (code "87") (name "unconnected-(U4-RESV-Pad19)") (class "Default")
      (node (ref "U4") (pin "19") (pinfunction "RESV_19") (pintype "passive"))
    )
    (net (code "88") (name "unconnected-(XS1-D+-Pad3)") (class "Default")
      (node (ref "XS1") (pin "3") (pinfunction "D+_3") (pintype "passive"))
    )
    (net (code "89") (name "unconnected-(XS1-D--Pad2)") (class "Default")
      (node (ref "XS1") (pin "2") (pinfunction "D-_2") (pintype "passive"))
    )
    (net (code "90") (name "unconnected-(XS1-ID-Pad4)") (class "Default")
      (node (ref "XS1") (pin "4") (pinfunction "ID_4") (pintype "passive"))
    )
  )
)
